# ESP32-Proto2-LayoutB-SAM-9-17.net
KiCad netlist of a schematic drawn in EAGLE
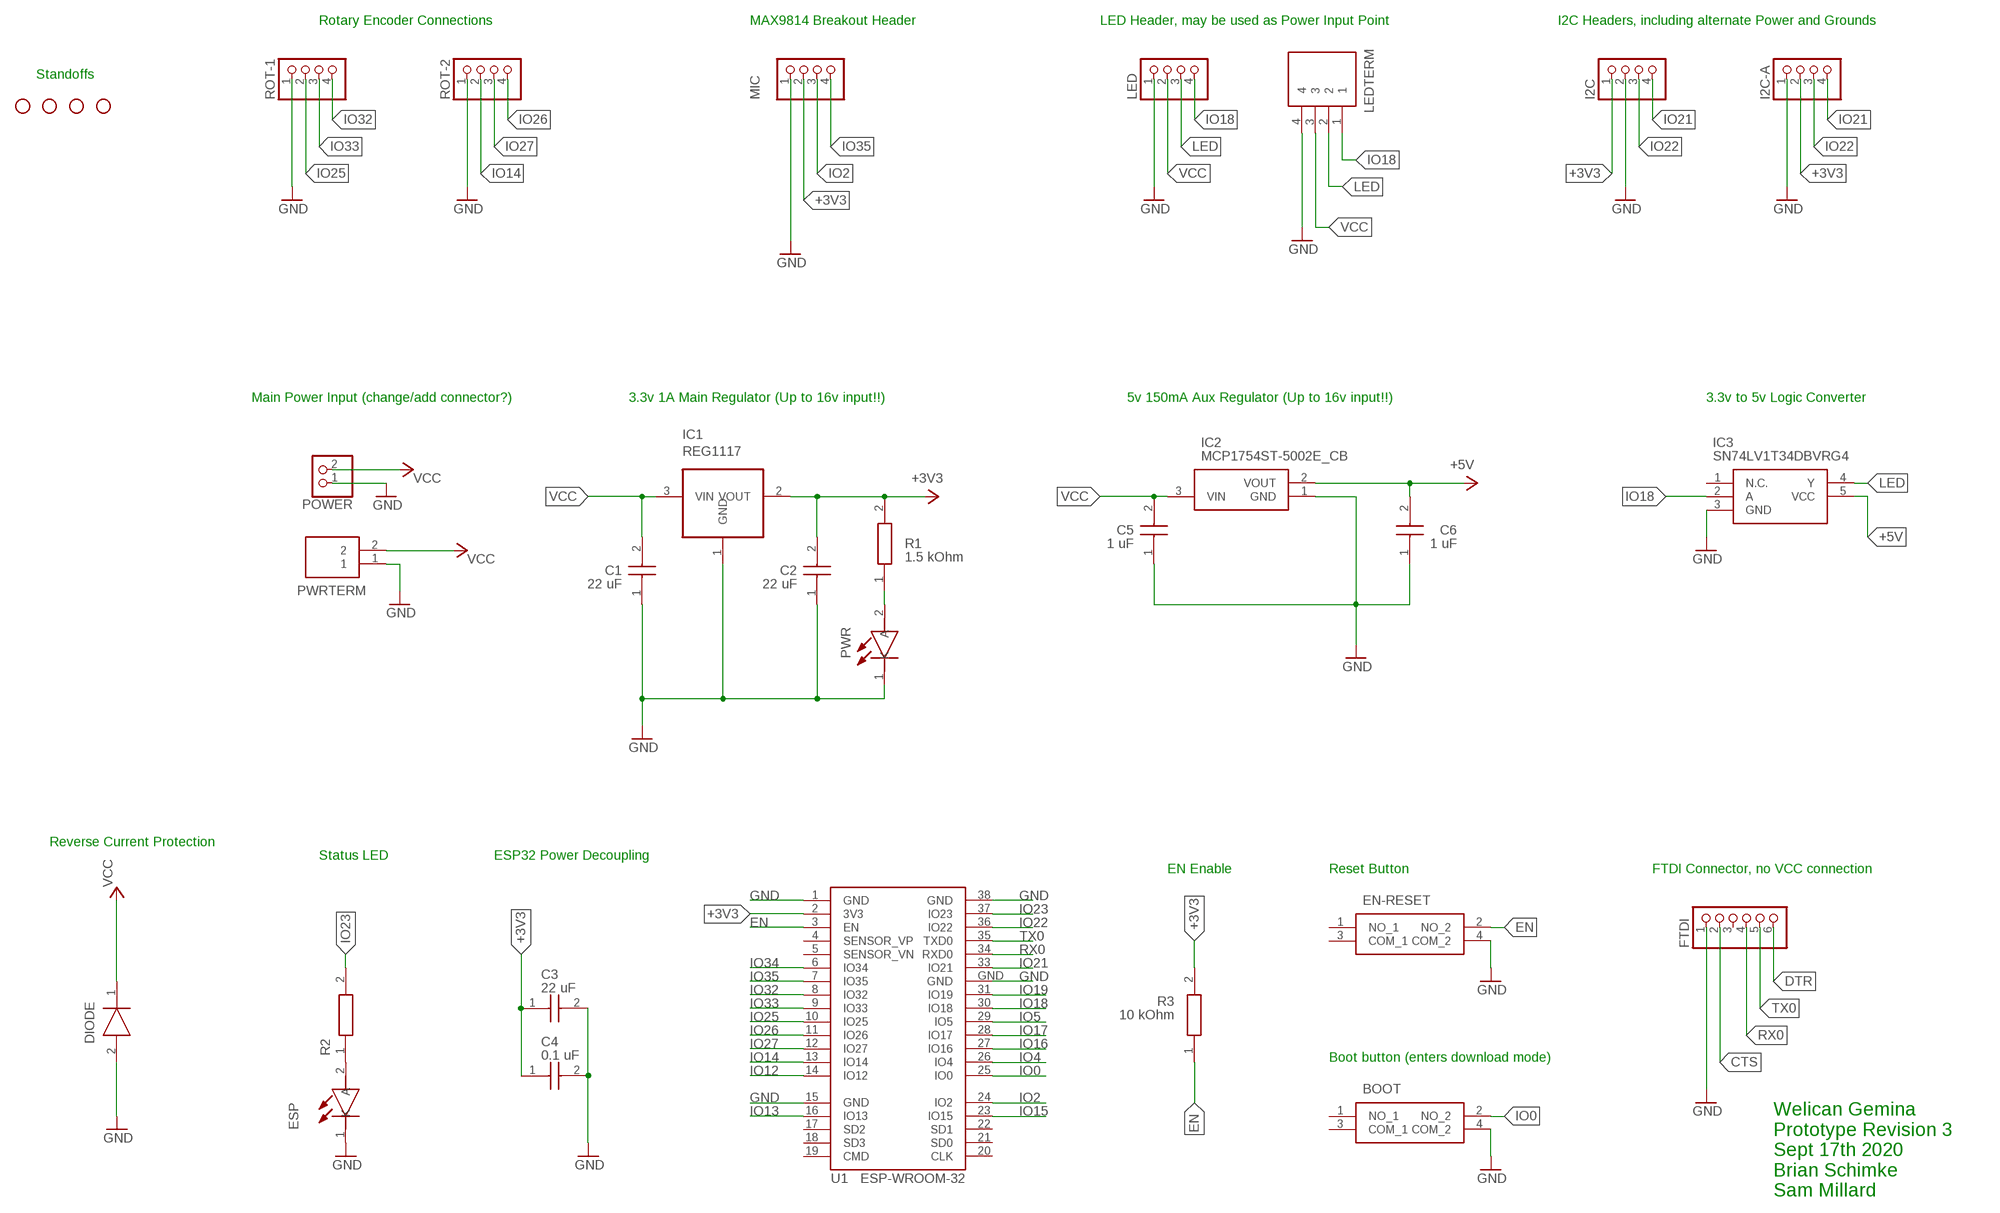
[diagram p0: schematic, sheet 1]

(export (version "E")
  (design (tool "Eeschema 10.0.6"))
  (components
    (comp (ref "BOOT")
      (value "PTS647SK70SMTR2LFS")
      (footprint "eagle-import:PTS647SK70SMTR2LFS")
      (fields (field (name "MOUSER_PART_NUMBER") "611-PTS647SK70SMTR2L"))
      (libsource (lib "eagle-import") (part "PTS647SK70SMTR2LFS"))
    )
    (comp (ref "C1")
      (value "22 uF")
      (footprint "eagle-import:CAPC3216X180N")
      (fields
        (field (name "MANUFACTURER_PART_NUMBER") "C1206C226M4PACTU")
        (field (name "MOUSER_PART_NUMBER") "80-C1206C226M4P")
      )
      (libsource (lib "eagle-import") (part "C1206C226M4PACTU"))
    )
    (comp (ref "C2")
      (value "22 uF")
      (footprint "eagle-import:CAPC3216X180N")
      (fields
        (field (name "MANUFACTURER_PART_NUMBER") "C1206C226M4PACTU")
        (field (name "MOUSER_PART_NUMBER") "80-C1206C226M4P")
      )
      (libsource (lib "eagle-import") (part "C1206C226M4PACTU"))
    )
    (comp (ref "C3")
      (value "22 uF")
      (footprint "eagle-import:CAPC3216X180N")
      (fields
        (field (name "MANUFACTURER_PART_NUMBER") "C1206C226M4PACTU")
        (field (name "MOUSER_PART_NUMBER") "80-C1206C226M4P")
      )
      (libsource (lib "eagle-import") (part "C1206C226M4PACTU"))
    )
    (comp (ref "C4")
      (value "0.1 uF")
      (footprint "eagle-import:CAPC3216X180N")
      (fields
        (field (name "MANUFACTURER_PART_NUMBER") "C1206C226M4PACTU")
        (field (name "MOUSER_PART_NUMBER") "80-C1206C226M4P")
      )
      (libsource (lib "eagle-import") (part "C1206C226M4PACTU"))
    )
    (comp (ref "C5")
      (value "1 uF")
      (footprint "eagle-import:CAPC3216X180N")
      (fields
        (field (name "MANUFACTURER_PART_NUMBER") "C1206C226M4PACTU")
        (field (name "MOUSER_PART_NUMBER") "80-C1206C226M4P")
      )
      (libsource (lib "eagle-import") (part "C1206C226M4PACTU"))
    )
    (comp (ref "C6")
      (value "1 uF")
      (footprint "eagle-import:CAPC3216X180N")
      (fields
        (field (name "MANUFACTURER_PART_NUMBER") "C1206C226M4PACTU")
        (field (name "MOUSER_PART_NUMBER") "80-C1206C226M4P")
      )
      (libsource (lib "eagle-import") (part "C1206C226M4PACTU"))
    )
    (comp (ref "DIODE")
      (value "RS3GB-13-F")
      (footprint "eagle-import:DIOM5336X250N")
      (fields (field (name "MOUSER_PART_NUMBER") "621-RS3GB-13-F"))
      (libsource (lib "eagle-import") (part "RS3GB-13-F"))
    )
    (comp (ref "EN-RESET")
      (value "PTS647SK70SMTR2LFS")
      (footprint "eagle-import:PTS647SK70SMTR2LFS")
      (fields (field (name "MOUSER_PART_NUMBER") "611-PTS647SK70SMTR2L"))
      (libsource (lib "eagle-import") (part "PTS647SK70SMTR2LFS"))
    )
    (comp (ref "ESP")
      (value "150120AS75000")
      (footprint "eagle-import:LEDSC320X160X78-2N")
      (fields (field (name "MOUSER_PART_NUMBER") "710-150120AS75000"))
      (libsource (lib "eagle-import") (part "150120AS75000"))
    )
    (comp (ref "FTDI")
      (value "PINHD-1X6")
      (footprint "eagle-import:1X06")
      (libsource (lib "eagle-import") (part "PINHD-1X6"))
    )
    (comp (ref "H1")
      (value "STAND-OFF")
      (footprint "eagle-import:STAND-OFF")
      (libsource (lib "eagle-import") (part "STAND-OFF"))
    )
    (comp (ref "H2")
      (value "STAND-OFF")
      (footprint "eagle-import:STAND-OFF")
      (libsource (lib "eagle-import") (part "STAND-OFF"))
    )
    (comp (ref "H3")
      (value "STAND-OFF")
      (footprint "eagle-import:STAND-OFF")
      (libsource (lib "eagle-import") (part "STAND-OFF"))
    )
    (comp (ref "H4")
      (value "STAND-OFF")
      (footprint "eagle-import:STAND-OFF")
      (libsource (lib "eagle-import") (part "STAND-OFF"))
    )
    (comp (ref "I2C")
      (value "PINHD-1X4")
      (footprint "eagle-import:1X04")
      (libsource (lib "eagle-import") (part "PINHD-1X4"))
    )
    (comp (ref "I2C-A")
      (value "PINHD-1X4")
      (footprint "eagle-import:1X04")
      (libsource (lib "eagle-import") (part "PINHD-1X4"))
    )
    (comp (ref "IC1")
      (value "REG1117")
      (footprint "eagle-import:SOT223")
      (libsource (lib "eagle-import") (part "REG1117"))
    )
    (comp (ref "IC2")
      (value "MCP1754ST-5002E_CB")
      (footprint "eagle-import:SOT95P255X145-3N")
      (fields
        (field (name "MANUFACTURER_PART_NUMBER") "MCP1754ST-5002E/CB")
        (field (name "MOUSER_PART_NUMBER") "579-MCP1754T-5002ECB")
      )
      (libsource (lib "eagle-import") (part "MCP1754ST-5002E_CB"))
    )
    (comp (ref "IC3")
      (value "SN74LV1T34DBVRG4")
      (footprint "eagle-import:SOT95P280X145-5N")
      (fields (field (name "MOUSER_PART_NUMBER") "595-SN74LV1T34DBVRG4"))
      (libsource (lib "eagle-import") (part "SN74LV1T34DBVRG4"))
    )
    (comp (ref "LED")
      (value "PINHD-1X4")
      (footprint "eagle-import:1X04")
      (libsource (lib "eagle-import") (part "PINHD-1X4"))
    )
    (comp (ref "LEDTERM")
      (value "1984633")
      (footprint "eagle-import:1984633")
      (fields (field (name "MOUSER_PART_NUMBER") "651-1984633"))
      (libsource (lib "eagle-import") (part "1984633"))
    )
    (comp (ref "MIC")
      (value "PINHD-1X4")
      (footprint "eagle-import:1X04")
      (libsource (lib "eagle-import") (part "PINHD-1X4"))
    )
    (comp (ref "POWER")
      (value "PINHD-1X2")
      (footprint "eagle-import:1X02")
      (libsource (lib "eagle-import") (part "PINHD-1X2"))
    )
    (comp (ref "PWR")
      (value "150120AS75000")
      (footprint "eagle-import:LEDSC320X160X78-2N")
      (fields (field (name "MOUSER_PART_NUMBER") "710-150120AS75000"))
      (libsource (lib "eagle-import") (part "150120AS75000"))
    )
    (comp (ref "PWRTERM")
      (value "1984617")
      (footprint "eagle-import:1984617")
      (libsource (lib "eagle-import") (part "1984617"))
    )
    (comp (ref "R1")
      (value "1.5 kOhm")
      (footprint "eagle-import:RESC3216X60N")
      (fields
        (field (name "MANUFACTURER_PART_NUMBER") "CRCW12061K00FKEB")
        (field (name "MOUSER_PART_NUMBER") "71-CRCW12061K00FKEB")
      )
      (libsource (lib "eagle-import") (part "CRCW12061K00FKEB"))
    )
    (comp (ref "R2")
      (value "CRCW12061K00FKEB")
      (footprint "eagle-import:RESC3216X60N")
      (fields (field (name "MOUSER_PART_NUMBER") "71-CRCW12061K00FKEB"))
      (libsource (lib "eagle-import") (part "CRCW12061K00FKEB"))
    )
    (comp (ref "R3")
      (value "10 kOhm")
      (footprint "eagle-import:RESC3216X60N")
      (fields
        (field (name "MANUFACTURER_PART_NUMBER") "CRCW12061K00FKEB")
        (field (name "MOUSER_PART_NUMBER") "71-CRCW12061K00FKEB")
      )
      (libsource (lib "eagle-import") (part "CRCW12061K00FKEB"))
    )
    (comp (ref "ROT-1")
      (value "PINHD-1X4")
      (footprint "eagle-import:1X04")
      (libsource (lib "eagle-import") (part "PINHD-1X4"))
    )
    (comp (ref "ROT-2")
      (value "PINHD-1X4")
      (footprint "eagle-import:1X04")
      (libsource (lib "eagle-import") (part "PINHD-1X4"))
    )
    (comp (ref "U1")
      (value "ESP-WROOM-32")
      (footprint "eagle-import:ESP-WROOM-32")
      (libsource (lib "eagle-import") (part "ESP-WROOM-32"))
    )
  )
  (nets
    (net (code "1") (name "+3V3") (class "Default")
      (node (ref "C2") (pin "2") (pinfunction "2_2") (pintype "bidirectional"))
      (node (ref "C3") (pin "1") (pinfunction "1_1") (pintype "bidirectional"))
      (node (ref "C4") (pin "1") (pinfunction "1_1") (pintype "bidirectional"))
      (node (ref "I2C") (pin "1") (pinfunction "1_1") (pintype "passive"))
      (node (ref "I2C-A") (pin "2") (pinfunction "2_2") (pintype "passive"))
      (node (ref "IC1") (pin "2") (pinfunction "VOUT_2") (pintype "output"))
      (node (ref "MIC") (pin "2") (pinfunction "2_2") (pintype "passive"))
      (node (ref "R1") (pin "2") (pinfunction "2_2") (pintype "bidirectional"))
      (node (ref "R3") (pin "2") (pinfunction "2_2") (pintype "bidirectional"))
      (node (ref "U1") (pin "2") (pinfunction "3V3_2") (pintype "power_in"))
    )
    (net (code "2") (name "+5V") (class "Default")
      (node (ref "C6") (pin "2") (pinfunction "2_2") (pintype "bidirectional"))
      (node (ref "IC2") (pin "2") (pinfunction "VOUT_2") (pintype "bidirectional"))
      (node (ref "IC3") (pin "5") (pinfunction "VCC_5") (pintype "bidirectional"))
    )
    (net (code "3") (name "/IO4") (class "Default")
      (node (ref "U1") (pin "26") (pinfunction "IO4_26") (pintype "bidirectional"))
    )
    (net (code "4") (name "/IO5") (class "Default")
      (node (ref "U1") (pin "29") (pinfunction "IO5_29") (pintype "bidirectional"))
    )
    (net (code "5") (name "/IO12") (class "Default")
      (node (ref "U1") (pin "14") (pinfunction "IO12_14") (pintype "bidirectional"))
    )
    (net (code "6") (name "/IO13") (class "Default")
      (node (ref "U1") (pin "16") (pinfunction "IO13_16") (pintype "bidirectional"))
    )
    (net (code "7") (name "/IO15") (class "Default")
      (node (ref "U1") (pin "23") (pinfunction "IO15_23") (pintype "bidirectional"))
    )
    (net (code "8") (name "/IO16") (class "Default")
      (node (ref "U1") (pin "27") (pinfunction "IO16_27") (pintype "bidirectional"))
    )
    (net (code "9") (name "/IO17") (class "Default")
      (node (ref "U1") (pin "28") (pinfunction "IO17_28") (pintype "bidirectional"))
    )
    (net (code "10") (name "/IO19") (class "Default")
      (node (ref "U1") (pin "31") (pinfunction "IO19_31") (pintype "bidirectional"))
    )
    (net (code "11") (name "/IO34") (class "Default")
      (node (ref "U1") (pin "6") (pinfunction "IO34_6") (pintype "bidirectional"))
    )
    (net (code "12") (name "CTS") (class "Default")
      (node (ref "FTDI") (pin "2") (pinfunction "2_2") (pintype "passive"))
    )
    (net (code "13") (name "DTR") (class "Default")
      (node (ref "FTDI") (pin "6") (pinfunction "6_6") (pintype "passive"))
    )
    (net (code "14") (name "EN") (class "Default")
      (node (ref "EN-RESET") (pin "2") (pinfunction "NO_2_2") (pintype "bidirectional"))
      (node (ref "R3") (pin "1") (pinfunction "1_1") (pintype "bidirectional"))
      (node (ref "U1") (pin "3") (pinfunction "EN_3") (pintype "input"))
    )
    (net (code "15") (name "GND") (class "Default")
      (node (ref "BOOT") (pin "4") (pinfunction "COM_2_4") (pintype "bidirectional"))
      (node (ref "C1") (pin "1") (pinfunction "1_1") (pintype "bidirectional"))
      (node (ref "C2") (pin "1") (pinfunction "1_1") (pintype "bidirectional"))
      (node (ref "C3") (pin "2") (pinfunction "2_2") (pintype "bidirectional"))
      (node (ref "C4") (pin "2") (pinfunction "2_2") (pintype "bidirectional"))
      (node (ref "C5") (pin "1") (pinfunction "1_1") (pintype "bidirectional"))
      (node (ref "C6") (pin "1") (pinfunction "1_1") (pintype "bidirectional"))
      (node (ref "DIODE") (pin "2") (pinfunction "A_2") (pintype "bidirectional"))
      (node (ref "EN-RESET") (pin "4") (pinfunction "COM_2_4") (pintype "bidirectional"))
      (node (ref "ESP") (pin "1") (pinfunction "K_1") (pintype "bidirectional"))
      (node (ref "FTDI") (pin "1") (pinfunction "1_1") (pintype "passive"))
      (node (ref "I2C") (pin "2") (pinfunction "2_2") (pintype "passive"))
      (node (ref "I2C-A") (pin "1") (pinfunction "1_1") (pintype "passive"))
      (node (ref "IC1") (pin "1") (pinfunction "GND_1") (pintype "power_in"))
      (node (ref "IC2") (pin "1") (pinfunction "GND_1") (pintype "bidirectional"))
      (node (ref "IC3") (pin "3") (pinfunction "GND_3") (pintype "bidirectional"))
      (node (ref "LED") (pin "1") (pinfunction "1_1") (pintype "passive"))
      (node (ref "LEDTERM") (pin "4") (pinfunction "4_4") (pintype "bidirectional"))
      (node (ref "MIC") (pin "1") (pinfunction "1_1") (pintype "passive"))
      (node (ref "POWER") (pin "1") (pinfunction "1_1") (pintype "passive"))
      (node (ref "PWR") (pin "1") (pinfunction "K_1") (pintype "bidirectional"))
      (node (ref "PWRTERM") (pin "1") (pinfunction "1_1") (pintype "bidirectional"))
      (node (ref "ROT-1") (pin "1") (pinfunction "1_1") (pintype "passive"))
      (node (ref "ROT-2") (pin "1") (pinfunction "1_1") (pintype "passive"))
      (node (ref "U1") (pin "1") (pinfunction "GND_1") (pintype "power_in"))
      (node (ref "U1") (pin "15") (pinfunction "GND_15") (pintype "power_in"))
      (node (ref "U1") (pin "38") (pinfunction "GND_38") (pintype "power_in"))
      (node (ref "U1") (pin "GND") (pinfunction "GND_GND") (pintype "power_in"))
    )
    (net (code "16") (name "IO0") (class "Default")
      (node (ref "BOOT") (pin "2") (pinfunction "NO_2_2") (pintype "bidirectional"))
      (node (ref "U1") (pin "25") (pinfunction "IO0_25") (pintype "bidirectional"))
    )
    (net (code "17") (name "IO2") (class "Default")
      (node (ref "MIC") (pin "3") (pinfunction "3_3") (pintype "passive"))
      (node (ref "U1") (pin "24") (pinfunction "IO2_24") (pintype "bidirectional"))
    )
    (net (code "18") (name "IO14") (class "Default")
      (node (ref "ROT-2") (pin "2") (pinfunction "2_2") (pintype "passive"))
      (node (ref "U1") (pin "13") (pinfunction "IO14_13") (pintype "bidirectional"))
    )
    (net (code "19") (name "IO18") (class "Default")
      (node (ref "IC3") (pin "2") (pinfunction "A_2") (pintype "bidirectional"))
      (node (ref "LED") (pin "4") (pinfunction "4_4") (pintype "passive"))
      (node (ref "LEDTERM") (pin "1") (pinfunction "1_1") (pintype "bidirectional"))
      (node (ref "U1") (pin "30") (pinfunction "IO18_30") (pintype "bidirectional"))
    )
    (net (code "20") (name "IO21") (class "Default")
      (node (ref "I2C") (pin "4") (pinfunction "4_4") (pintype "passive"))
      (node (ref "I2C-A") (pin "4") (pinfunction "4_4") (pintype "passive"))
      (node (ref "U1") (pin "33") (pinfunction "IO21_33") (pintype "bidirectional"))
    )
    (net (code "21") (name "IO22") (class "Default")
      (node (ref "I2C") (pin "3") (pinfunction "3_3") (pintype "passive"))
      (node (ref "I2C-A") (pin "3") (pinfunction "3_3") (pintype "passive"))
      (node (ref "U1") (pin "36") (pinfunction "IO22_36") (pintype "bidirectional"))
    )
    (net (code "22") (name "IO23") (class "Default")
      (node (ref "R2") (pin "2") (pinfunction "2_2") (pintype "bidirectional"))
      (node (ref "U1") (pin "37") (pinfunction "IO23_37") (pintype "bidirectional"))
    )
    (net (code "23") (name "IO25") (class "Default")
      (node (ref "ROT-1") (pin "2") (pinfunction "2_2") (pintype "passive"))
      (node (ref "U1") (pin "10") (pinfunction "IO25_10") (pintype "bidirectional"))
    )
    (net (code "24") (name "IO26") (class "Default")
      (node (ref "ROT-2") (pin "4") (pinfunction "4_4") (pintype "passive"))
      (node (ref "U1") (pin "11") (pinfunction "IO26_11") (pintype "bidirectional"))
    )
    (net (code "25") (name "IO27") (class "Default")
      (node (ref "ROT-2") (pin "3") (pinfunction "3_3") (pintype "passive"))
      (node (ref "U1") (pin "12") (pinfunction "IO27_12") (pintype "bidirectional"))
    )
    (net (code "26") (name "IO32") (class "Default")
      (node (ref "ROT-1") (pin "4") (pinfunction "4_4") (pintype "passive"))
      (node (ref "U1") (pin "8") (pinfunction "IO32_8") (pintype "bidirectional"))
    )
    (net (code "27") (name "IO33") (class "Default")
      (node (ref "ROT-1") (pin "3") (pinfunction "3_3") (pintype "passive"))
      (node (ref "U1") (pin "9") (pinfunction "IO33_9") (pintype "bidirectional"))
    )
    (net (code "28") (name "IO35") (class "Default")
      (node (ref "MIC") (pin "4") (pinfunction "4_4") (pintype "passive"))
      (node (ref "U1") (pin "7") (pinfunction "IO35_7") (pintype "bidirectional"))
    )
    (net (code "29") (name "LED") (class "Default")
      (node (ref "IC3") (pin "4") (pinfunction "Y_4") (pintype "bidirectional"))
      (node (ref "LED") (pin "3") (pinfunction "3_3") (pintype "passive"))
      (node (ref "LEDTERM") (pin "2") (pinfunction "2_2") (pintype "bidirectional"))
    )
    (net (code "30") (name "Net-(ESP-A)") (class "Default")
      (node (ref "ESP") (pin "2") (pinfunction "A_2") (pintype "bidirectional"))
      (node (ref "R2") (pin "1") (pinfunction "1_1") (pintype "bidirectional"))
    )
    (net (code "31") (name "Net-(PWR-A)") (class "Default")
      (node (ref "PWR") (pin "2") (pinfunction "A_2") (pintype "bidirectional"))
      (node (ref "R1") (pin "1") (pinfunction "1_1") (pintype "bidirectional"))
    )
    (net (code "32") (name "RX0") (class "Default")
      (node (ref "FTDI") (pin "4") (pinfunction "4_4") (pintype "passive"))
      (node (ref "U1") (pin "34") (pinfunction "RXD0_34") (pintype "bidirectional"))
    )
    (net (code "33") (name "TX0") (class "Default")
      (node (ref "FTDI") (pin "5") (pinfunction "5_5") (pintype "passive"))
      (node (ref "U1") (pin "35") (pinfunction "TXD0_35") (pintype "bidirectional"))
    )
    (net (code "34") (name "VCC") (class "Default")
      (node (ref "C1") (pin "2") (pinfunction "2_2") (pintype "bidirectional"))
      (node (ref "C5") (pin "2") (pinfunction "2_2") (pintype "bidirectional"))
      (node (ref "DIODE") (pin "1") (pinfunction "K_1") (pintype "bidirectional"))
      (node (ref "IC1") (pin "3") (pinfunction "VIN_3") (pintype "input"))
      (node (ref "IC2") (pin "3") (pinfunction "VIN_3") (pintype "bidirectional"))
      (node (ref "LED") (pin "2") (pinfunction "2_2") (pintype "passive"))
      (node (ref "LEDTERM") (pin "3") (pinfunction "3_3") (pintype "bidirectional"))
      (node (ref "POWER") (pin "2") (pinfunction "2_2") (pintype "passive"))
      (node (ref "PWRTERM") (pin "2") (pinfunction "2_2") (pintype "bidirectional"))
    )
    (net (code "35") (name "unconnected-(BOOT-COM_1-Pad3)") (class "Default")
      (node (ref "BOOT") (pin "3") (pinfunction "COM_1_3") (pintype "bidirectional"))
    )
    (net (code "36") (name "unconnected-(BOOT-NO_1-Pad1)") (class "Default")
      (node (ref "BOOT") (pin "1") (pinfunction "NO_1_1") (pintype "bidirectional"))
    )
    (net (code "37") (name "unconnected-(EN-RESET-COM_1-Pad3)") (class "Default")
      (node (ref "EN-RESET") (pin "3") (pinfunction "COM_1_3") (pintype "bidirectional"))
    )
    (net (code "38") (name "unconnected-(EN-RESET-NO_1-Pad1)") (class "Default")
      (node (ref "EN-RESET") (pin "1") (pinfunction "NO_1_1") (pintype "bidirectional"))
    )
    (net (code "39") (name "unconnected-(FTDI-Pad3)") (class "Default")
      (node (ref "FTDI") (pin "3") (pinfunction "3_3") (pintype "passive"))
    )
    (net (code "40") (name "unconnected-(IC3-N.C.-Pad1)") (class "Default")
      (node (ref "IC3") (pin "1") (pinfunction "N.C._1") (pintype "no_connect"))
    )
    (net (code "41") (name "unconnected-(U1-CLK-Pad20)") (class "Default")
      (node (ref "U1") (pin "20") (pinfunction "CLK_20") (pintype "bidirectional"))
    )
    (net (code "42") (name "unconnected-(U1-CMD-Pad19)") (class "Default")
      (node (ref "U1") (pin "19") (pinfunction "CMD_19") (pintype "bidirectional"))
    )
    (net (code "43") (name "unconnected-(U1-SD0-Pad21)") (class "Default")
      (node (ref "U1") (pin "21") (pinfunction "SD0_21") (pintype "bidirectional"))
    )
    (net (code "44") (name "unconnected-(U1-SD1-Pad22)") (class "Default")
      (node (ref "U1") (pin "22") (pinfunction "SD1_22") (pintype "bidirectional"))
    )
    (net (code "45") (name "unconnected-(U1-SD2-Pad17)") (class "Default")
      (node (ref "U1") (pin "17") (pinfunction "SD2_17") (pintype "bidirectional"))
    )
    (net (code "46") (name "unconnected-(U1-SD3-Pad18)") (class "Default")
      (node (ref "U1") (pin "18") (pinfunction "SD3_18") (pintype "bidirectional"))
    )
    (net (code "47") (name "unconnected-(U1-SENSOR_VN-Pad5)") (class "Default")
      (node (ref "U1") (pin "5") (pinfunction "SENSOR_VN_5") (pintype "bidirectional"))
    )
    (net (code "48") (name "unconnected-(U1-SENSOR_VP-Pad4)") (class "Default")
      (node (ref "U1") (pin "4") (pinfunction "SENSOR_VP_4") (pintype "bidirectional"))
    )
  )
)
